# MCU.net
KiCad netlist of a schematic drawn in Altium Designer
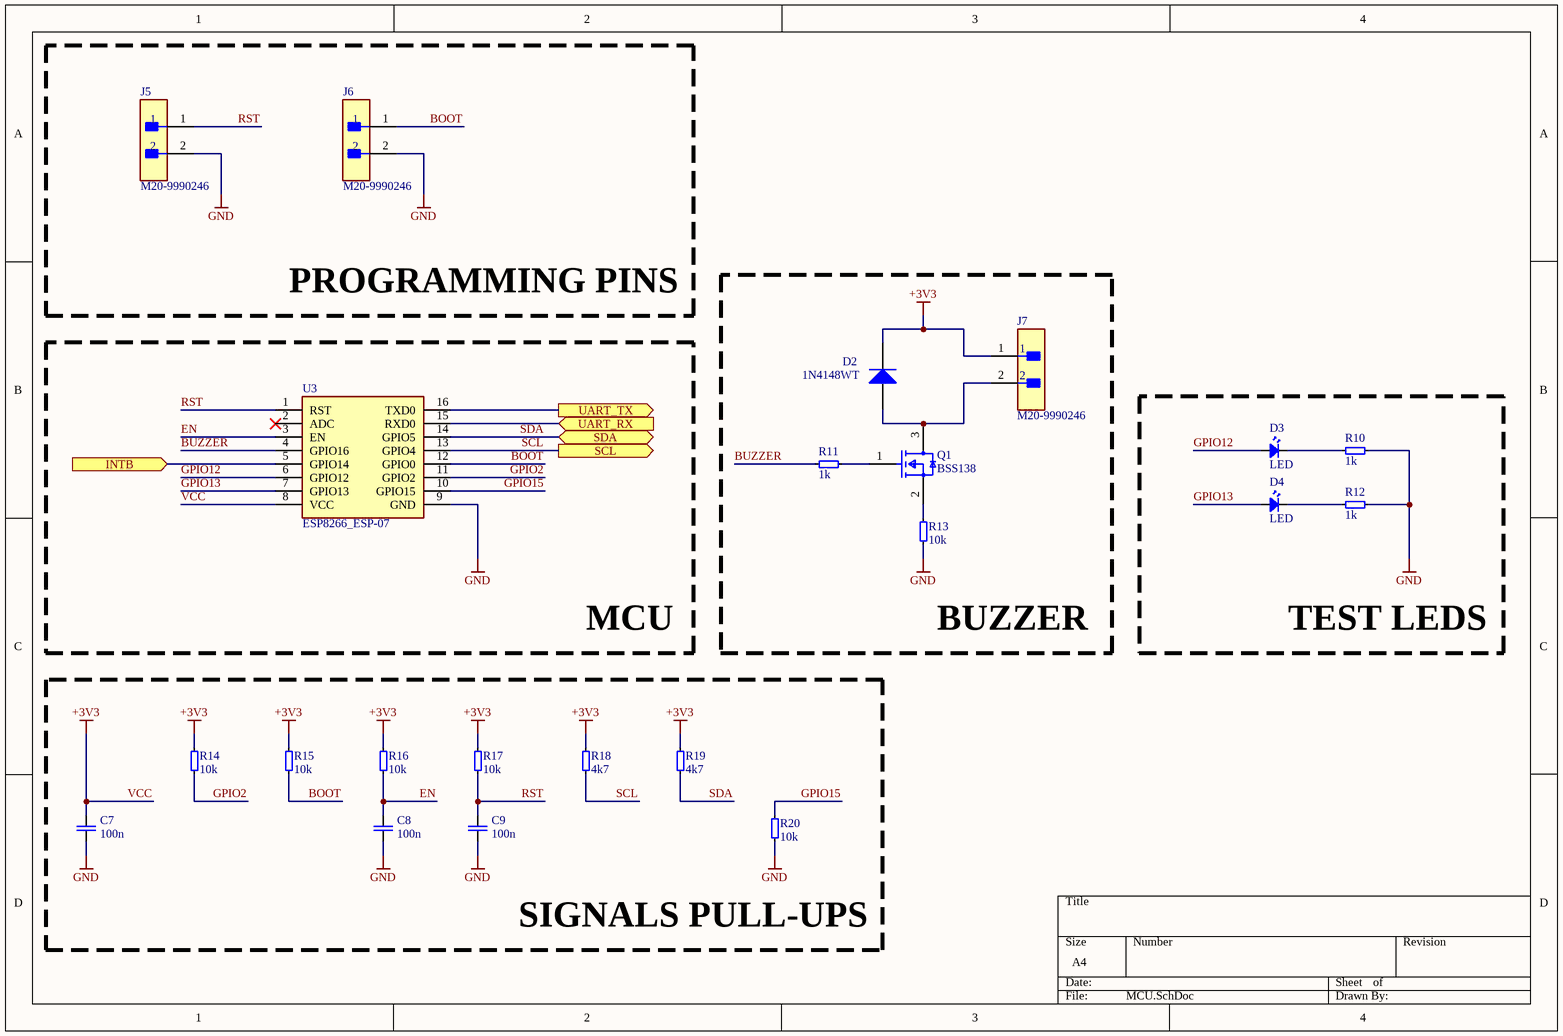
[diagram p0: MCU.SchDoc]

(export (version "E")
  (design (tool "Eeschema 10.0.6"))
  (components
    (comp (ref "C7")
      (value "100n")
      (footprint "C0603")
      (description "Generic 0603 SMD Ceramic Capacitor")
      (libsource (lib "PolSl Racing - Electrical") (part "Capacitor"))
    )
    (comp (ref "C8")
      (value "100n")
      (footprint "C0603")
      (description "Generic 0603 SMD Ceramic Capacitor")
      (libsource (lib "PolSl Racing - Electrical") (part "Capacitor"))
    )
    (comp (ref "C9")
      (value "100n")
      (footprint "C0603")
      (description "Generic 0603 SMD Ceramic Capacitor")
      (libsource (lib "PolSl Racing - Electrical") (part "Capacitor"))
    )
    (comp (ref "D2")
      (value "1N4148WT")
      (footprint "FAIR-SOD-523F-2_V")
      (description "High Conductance Fast Switching Diode, 75 V, -55 to 150 degC, 2-Pin SOD523F, RoHS")
      (fields (field (name "MANUFACTURER") "Fairchild Semiconductor"))
      (libsource (lib "Altium Content Vault") (part "FAIR-D_K1A2-2"))
    )
    (comp (ref "D3")
      (value "LED")
      (footprint "LED0603")
      (description "0603 LED")
      (libsource (lib "PolSl Racing - Electrical") (part "LED"))
    )
    (comp (ref "D4")
      (value "LED")
      (footprint "LED0603")
      (description "0603 LED")
      (libsource (lib "PolSl Racing - Electrical") (part "LED"))
    )
    (comp (ref "J5")
      (value "M20-9990246")
      (footprint "FP-M20-9990246-MFG")
      (description "CONN HEADER VERT 2POS 2.54MM")
      (fields
        (field (name "OCTOPART") "https://octopart.com/m20-9990246-harwin-2590635")
        (field (name "MANUFACTURER") "Harwin")
      )
      (libsource (lib "") (part "3bc925449376181038e59eaffc5286c_1"))
    )
    (comp (ref "J6")
      (value "M20-9990246")
      (footprint "FP-M20-9990246-MFG")
      (description "CONN HEADER VERT 2POS 2.54MM")
      (fields
        (field (name "OCTOPART") "https://octopart.com/m20-9990246-harwin-2590635")
        (field (name "MANUFACTURER") "Harwin")
      )
      (libsource (lib "") (part "3bc925449376181038e59eaffc5286c_1"))
    )
    (comp (ref "J7")
      (value "M20-9990246")
      (footprint "FP-M20-9990246-MFG")
      (description "CONN HEADER VERT 2POS 2.54MM")
      (fields
        (field (name "OCTOPART") "https://octopart.com/m20-9990246-harwin-2590635")
        (field (name "MANUFACTURER") "Harwin")
      )
      (libsource (lib "Altium Content Vault") (part "3bc925449376181038e59eaffc5286c"))
    )
    (comp (ref "Q1")
      (value "BSS138")
      (footprint "FP-318-08-IPC_B")
      (description "MOSFET N-CH 50V 220MA SOT-23")
      (libsource (lib "Altium Content Vault") (part "3b9c635fedb024a5347a57b145af9cc"))
    )
    (comp (ref "R10")
      (value "1k")
      (footprint "R0603")
      (description "Generic 0603 SMD Resistor")
      (libsource (lib "PolSl Racing - Electrical") (part "Resistor"))
    )
    (comp (ref "R11")
      (value "1k")
      (footprint "R0603")
      (description "Generic 0603 SMD Resistor")
      (libsource (lib "PolSl Racing - Electrical") (part "Resistor"))
    )
    (comp (ref "R12")
      (value "1k")
      (footprint "R0603")
      (description "Generic 0603 SMD Resistor")
      (libsource (lib "PolSl Racing - Electrical") (part "Resistor"))
    )
    (comp (ref "R13")
      (value "10k")
      (footprint "R0603")
      (description "Generic 0603 SMD Resistor")
      (libsource (lib "PolSl Racing - Electrical") (part "Resistor"))
    )
    (comp (ref "R14")
      (value "10k")
      (footprint "R0603")
      (description "Generic 0603 SMD Resistor")
      (libsource (lib "PolSl Racing - Electrical") (part "Resistor"))
    )
    (comp (ref "R15")
      (value "10k")
      (footprint "R0603")
      (description "Generic 0603 SMD Resistor")
      (libsource (lib "PolSl Racing - Electrical") (part "Resistor"))
    )
    (comp (ref "R16")
      (value "10k")
      (footprint "R0603")
      (description "Generic 0603 SMD Resistor")
      (libsource (lib "PolSl Racing - Electrical") (part "Resistor"))
    )
    (comp (ref "R17")
      (value "10k")
      (footprint "R0603")
      (description "Generic 0603 SMD Resistor")
      (libsource (lib "PolSl Racing - Electrical") (part "Resistor"))
    )
    (comp (ref "R18")
      (value "4k7")
      (footprint "R0603")
      (description "Generic 0603 SMD Resistor")
      (libsource (lib "PolSl Racing - Electrical") (part "Resistor"))
    )
    (comp (ref "R19")
      (value "4k7")
      (footprint "R0603")
      (description "Generic 0603 SMD Resistor")
      (libsource (lib "PolSl Racing - Electrical") (part "Resistor"))
    )
    (comp (ref "R20")
      (value "10k")
      (footprint "R0603")
      (description "Generic 0603 SMD Resistor")
      (libsource (lib "PolSl Racing - Electrical") (part "Resistor"))
    )
    (comp (ref "U3")
      (value "ESP8266_ESP-07")
      (footprint "SamacSys:ESP8266ESP07")
      (description "Connector")
      (fields (field (name "MANUFACTURER_PART_NUMBER") "ESP8266 ESP-07"))
      (libsource (lib "*") (part "ESP8266_ESP-07"))
    )
  )
  (nets
    (net (code "1") (name "+3V3") (class "Default")
      (node (ref "C7") (pin "2") (pinfunction "2_2") (pintype "passive"))
      (node (ref "D2") (pin "1") (pinfunction "K_1") (pintype "passive"))
      (node (ref "J7") (pin "1") (pinfunction "1_1") (pintype "passive"))
      (node (ref "R14") (pin "2") (pinfunction "2_2") (pintype "passive"))
      (node (ref "R15") (pin "2") (pinfunction "2_2") (pintype "passive"))
      (node (ref "R16") (pin "2") (pinfunction "2_2") (pintype "passive"))
      (node (ref "R17") (pin "2") (pinfunction "2_2") (pintype "passive"))
      (node (ref "R18") (pin "2") (pinfunction "2_2") (pintype "passive"))
      (node (ref "R19") (pin "2") (pinfunction "2_2") (pintype "passive"))
      (node (ref "U3") (pin "8") (pinfunction "VCC_8") (pintype "passive"))
    )
    (net (code "2") (name "/BOOT") (class "Default")
      (node (ref "J6") (pin "1") (pinfunction "1_1") (pintype "passive"))
      (node (ref "R15") (pin "1") (pinfunction "1_1") (pintype "passive"))
      (node (ref "U3") (pin "12") (pinfunction "GPIO0_12") (pintype "passive"))
    )
    (net (code "3") (name "/BUZZER") (class "Default")
      (node (ref "R11") (pin "2") (pinfunction "2_2") (pintype "passive"))
      (node (ref "U3") (pin "4") (pinfunction "GPIO16_4") (pintype "passive"))
    )
    (net (code "4") (name "/EN") (class "Default")
      (node (ref "C8") (pin "2") (pinfunction "2_2") (pintype "passive"))
      (node (ref "R16") (pin "1") (pinfunction "1_1") (pintype "passive"))
      (node (ref "U3") (pin "3") (pinfunction "EN_3") (pintype "passive"))
    )
    (net (code "5") (name "/GPIO2") (class "Default")
      (node (ref "R14") (pin "1") (pinfunction "1_1") (pintype "passive"))
      (node (ref "U3") (pin "11") (pinfunction "GPIO2_11") (pintype "passive"))
    )
    (net (code "6") (name "/GPIO12") (class "Default")
      (node (ref "D3") (pin "A") (pinfunction "A_A") (pintype "passive"))
      (node (ref "U3") (pin "6") (pinfunction "GPIO12_6") (pintype "passive"))
    )
    (net (code "7") (name "/GPIO13") (class "Default")
      (node (ref "D4") (pin "A") (pinfunction "A_A") (pintype "passive"))
      (node (ref "U3") (pin "7") (pinfunction "GPIO13_7") (pintype "passive"))
    )
    (net (code "8") (name "/GPIO15") (class "Default")
      (node (ref "R20") (pin "2") (pinfunction "2_2") (pintype "passive"))
      (node (ref "U3") (pin "10") (pinfunction "GPIO15_10") (pintype "passive"))
    )
    (net (code "9") (name "/INTB") (class "Default")
      (node (ref "U3") (pin "5") (pinfunction "GPIO14_5") (pintype "passive"))
    )
    (net (code "10") (name "/RST") (class "Default")
      (node (ref "C9") (pin "2") (pinfunction "2_2") (pintype "passive"))
      (node (ref "J5") (pin "1") (pinfunction "1_1") (pintype "passive"))
      (node (ref "R17") (pin "1") (pinfunction "1_1") (pintype "passive"))
      (node (ref "U3") (pin "1") (pinfunction "RST_1") (pintype "passive"))
    )
    (net (code "11") (name "/SCL") (class "Default")
      (node (ref "R18") (pin "1") (pinfunction "1_1") (pintype "passive"))
      (node (ref "U3") (pin "13") (pinfunction "GPIO4_13") (pintype "passive"))
    )
    (net (code "12") (name "/SDA") (class "Default")
      (node (ref "R19") (pin "1") (pinfunction "1_1") (pintype "passive"))
      (node (ref "U3") (pin "14") (pinfunction "GPIO5_14") (pintype "passive"))
    )
    (net (code "13") (name "/UART_RX") (class "Default")
      (node (ref "U3") (pin "15") (pinfunction "RXD0_15") (pintype "passive"))
    )
    (net (code "14") (name "/UART_TX") (class "Default")
      (node (ref "U3") (pin "16") (pinfunction "TXD0_16") (pintype "passive"))
    )
    (net (code "15") (name "GND") (class "Default")
      (node (ref "C7") (pin "1") (pinfunction "1_1") (pintype "passive"))
      (node (ref "C8") (pin "1") (pinfunction "1_1") (pintype "passive"))
      (node (ref "C9") (pin "1") (pinfunction "1_1") (pintype "passive"))
      (node (ref "J5") (pin "2") (pinfunction "2_2") (pintype "passive"))
      (node (ref "J6") (pin "2") (pinfunction "2_2") (pintype "passive"))
      (node (ref "R10") (pin "2") (pinfunction "2_2") (pintype "passive"))
      (node (ref "R12") (pin "2") (pinfunction "2_2") (pintype "passive"))
      (node (ref "R13") (pin "1") (pinfunction "1_1") (pintype "passive"))
      (node (ref "R20") (pin "1") (pinfunction "1_1") (pintype "passive"))
      (node (ref "U3") (pin "9") (pinfunction "GND_9") (pintype "passive"))
    )
    (net (code "16") (name "Net-(D2-A)") (class "Default")
      (node (ref "D2") (pin "2") (pinfunction "A_2") (pintype "passive"))
      (node (ref "J7") (pin "2") (pinfunction "2_2") (pintype "passive"))
      (node (ref "Q1") (pin "3") (pinfunction "D_3") (pintype "passive"))
    )
    (net (code "17") (name "Net-(D3-PadK)") (class "Default")
      (node (ref "D3") (pin "K") (pinfunction "K_K") (pintype "passive"))
      (node (ref "R10") (pin "1") (pinfunction "1_1") (pintype "passive"))
    )
    (net (code "18") (name "Net-(D4-PadK)") (class "Default")
      (node (ref "D4") (pin "K") (pinfunction "K_K") (pintype "passive"))
      (node (ref "R12") (pin "1") (pinfunction "1_1") (pintype "passive"))
    )
    (net (code "19") (name "Net-(Q1-G)") (class "Default")
      (node (ref "Q1") (pin "1") (pinfunction "G_1") (pintype "passive"))
      (node (ref "R11") (pin "1") (pinfunction "1_1") (pintype "passive"))
    )
    (net (code "20") (name "Net-(Q1-S)") (class "Default")
      (node (ref "Q1") (pin "2") (pinfunction "S_2") (pintype "passive"))
      (node (ref "R13") (pin "2") (pinfunction "2_2") (pintype "passive"))
    )
    (net (code "21") (name "unconnected-(U3-ADC-Pad2)") (class "Default")
      (node (ref "U3") (pin "2") (pinfunction "ADC_2") (pintype "passive+no_connect"))
    )
  )
)
